# xc2401_breakout.net
KiCad netlist of a schematic drawn in EAGLE
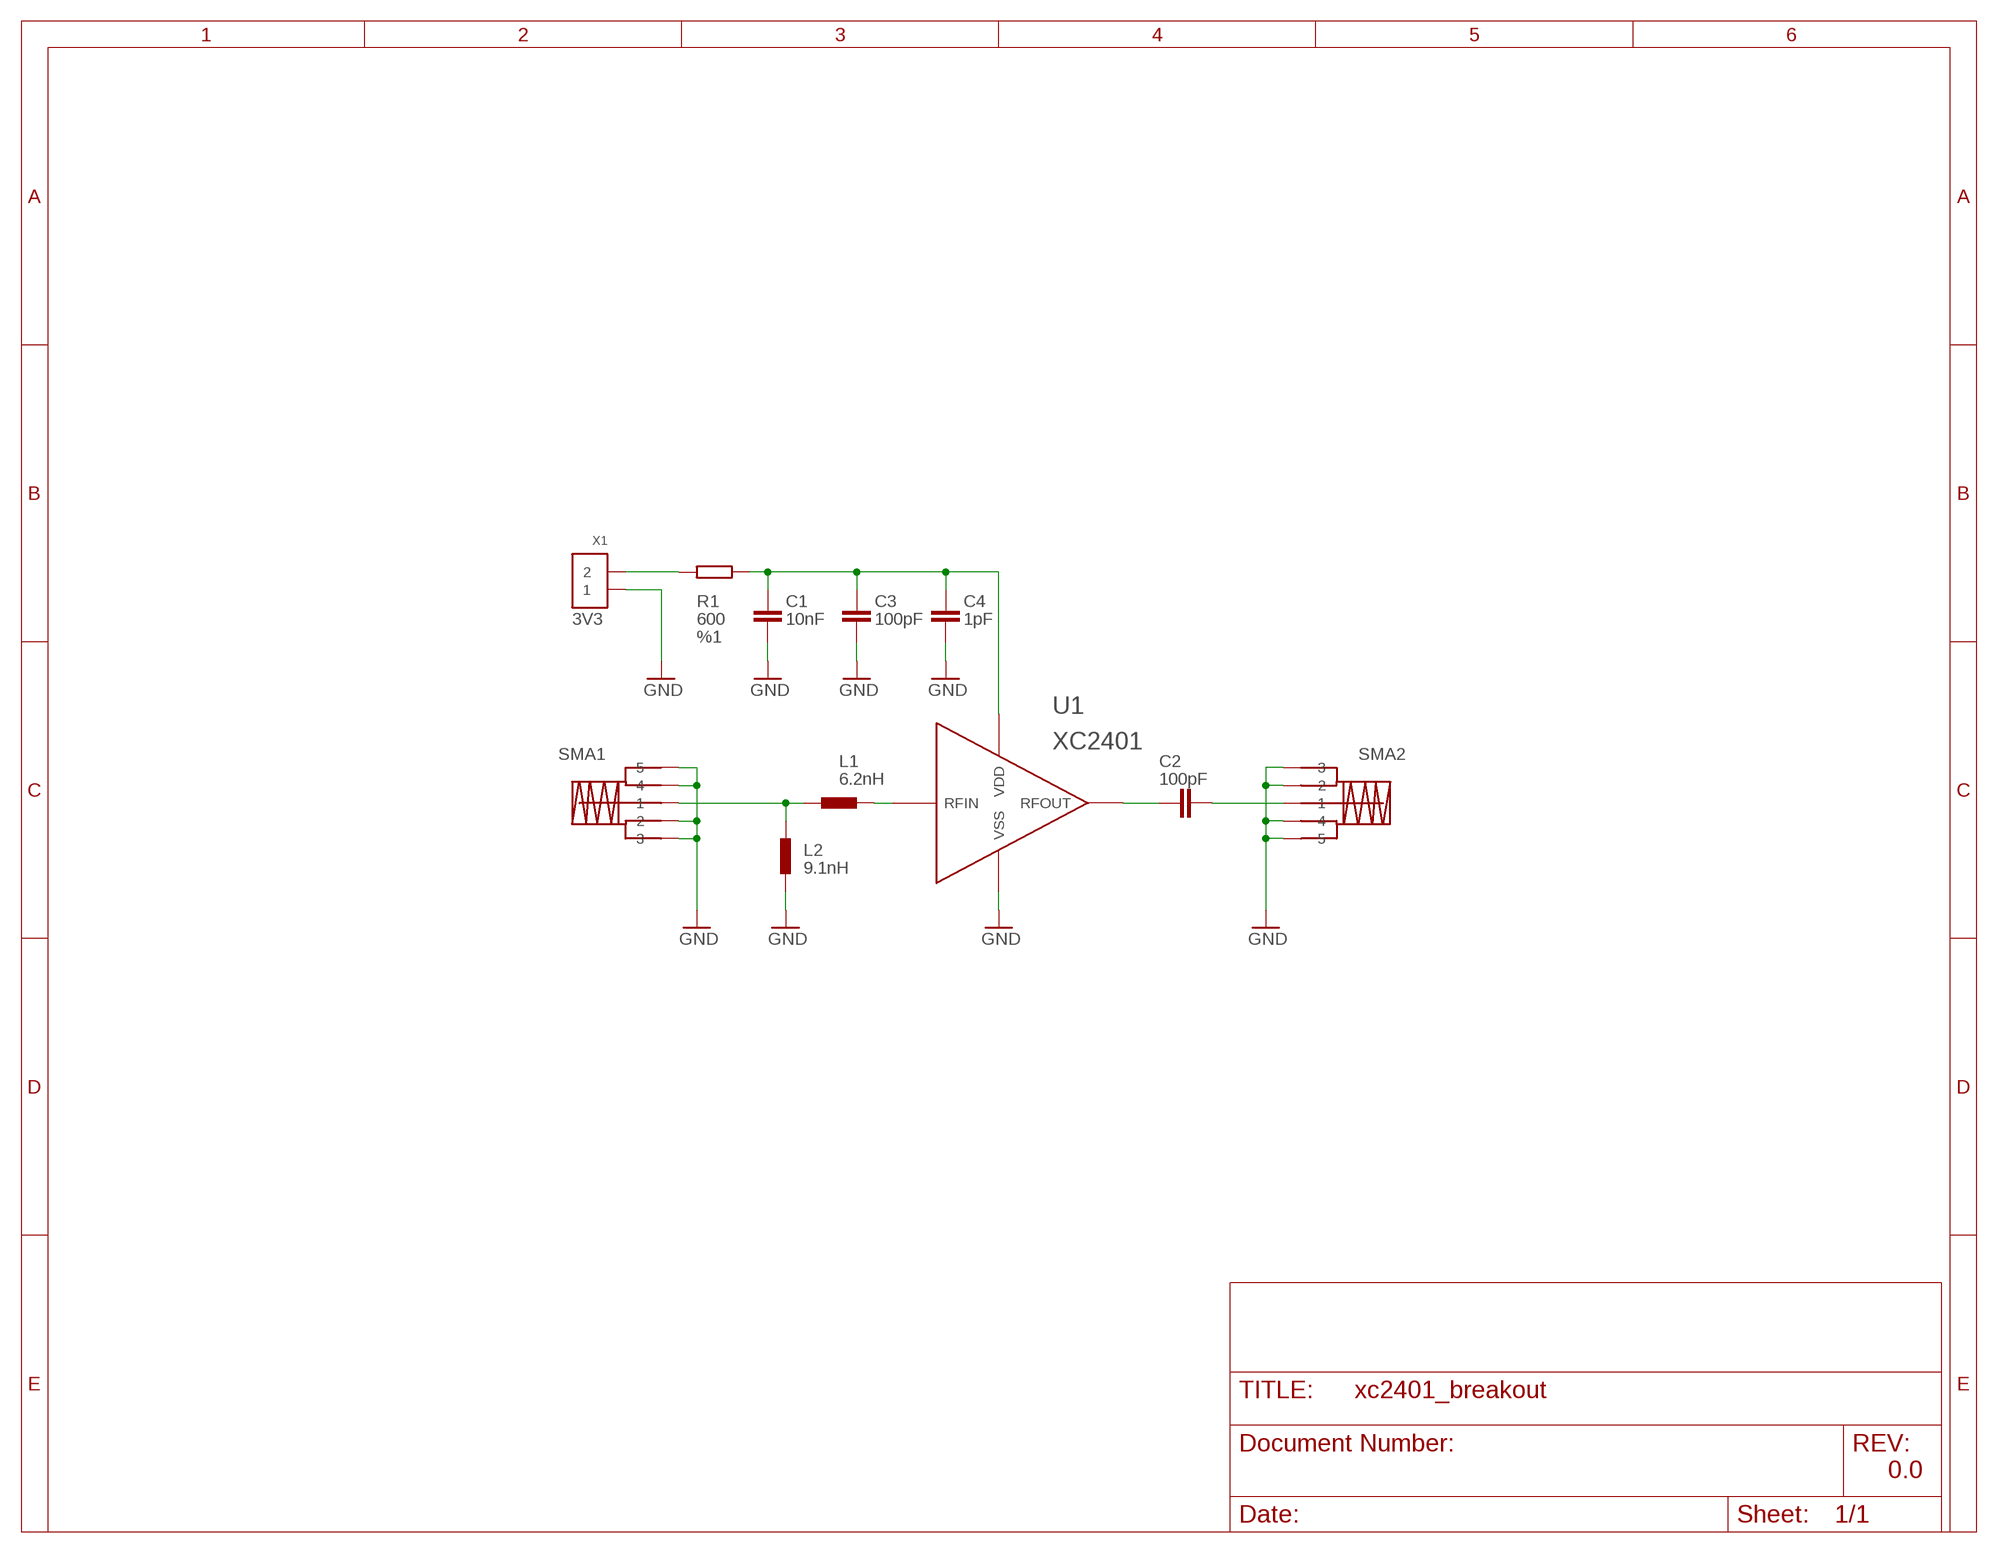
[diagram p0: schematic, sheet 1]

(export (version "E")
  (design (tool "Eeschema 10.0.6"))
  (components
    (comp (ref "C1")
      (value "10nF")
      (footprint "eagle-import:0402-CAP")
      (libsource (lib "eagle-import") (part "CAPACITOR-0402"))
    )
    (comp (ref "C2")
      (value "100pF")
      (footprint "eagle-import:0402-CAP")
      (libsource (lib "eagle-import") (part "CAPACITOR-0402"))
    )
    (comp (ref "C3")
      (value "100pF")
      (footprint "eagle-import:0402-CAP")
      (libsource (lib "eagle-import") (part "CAPACITOR-0402"))
    )
    (comp (ref "C4")
      (value "1pF")
      (footprint "eagle-import:0402-CAP")
      (libsource (lib "eagle-import") (part "CAPACITOR-0402"))
    )
    (comp (ref "L1")
      (value "6.2nH")
      (footprint "eagle-import:0402-IND")
      (libsource (lib "eagle-import") (part "INDUCTOR-0402"))
    )
    (comp (ref "L2")
      (value "9.1nH")
      (footprint "eagle-import:0402-IND")
      (libsource (lib "eagle-import") (part "INDUCTOR-0402"))
    )
    (comp (ref "R1")
      (value "600")
      (footprint "eagle-import:0402-RES")
      (libsource (lib "eagle-import") (part "RESISTOR-0402"))
    )
    (comp (ref "SMA1")
      (value "SMA_EDGE")
      (footprint "eagle-import:SMA_EDGE")
      (libsource (lib "eagle-import") (part "SMA_EDGE"))
    )
    (comp (ref "SMA2")
      (value "SMA_EDGE")
      (footprint "eagle-import:SMA_EDGE")
      (libsource (lib "eagle-import") (part "SMA_EDGE"))
    )
    (comp (ref "U1")
      (value "XC2401")
      (footprint "eagle-import:XC2401")
      (libsource (lib "eagle-import") (part "XC2401"))
    )
    (comp (ref "X1")
      (value "CONN_2-1-53261")
      (footprint "eagle-import:PB-53261-02")
      (libsource (lib "eagle-import") (part "CONN_2-1-53261"))
    )
  )
  (nets
    (net (code "1") (name "GND") (class "Default")
      (node (ref "C1") (pin "P$2") (pinfunction "2_P$2") (pintype "passive"))
      (node (ref "C3") (pin "P$2") (pinfunction "2_P$2") (pintype "passive"))
      (node (ref "C4") (pin "P$2") (pinfunction "2_P$2") (pintype "passive"))
      (node (ref "L2") (pin "P$1") (pinfunction "1_P$1") (pintype "passive"))
      (node (ref "SMA1") (pin "P2") (pinfunction "2_P2") (pintype "power_in"))
      (node (ref "SMA1") (pin "P3") (pinfunction "3_P3") (pintype "power_in"))
      (node (ref "SMA1") (pin "P4") (pinfunction "4_P4") (pintype "power_in"))
      (node (ref "SMA1") (pin "P5") (pinfunction "5_P5") (pintype "power_in"))
      (node (ref "SMA2") (pin "P2") (pinfunction "2_P2") (pintype "power_in"))
      (node (ref "SMA2") (pin "P3") (pinfunction "3_P3") (pintype "power_in"))
      (node (ref "SMA2") (pin "P4") (pinfunction "4_P4") (pintype "power_in"))
      (node (ref "SMA2") (pin "P5") (pinfunction "5_P5") (pintype "power_in"))
      (node (ref "U1") (pin "3") (pinfunction "VSS_3") (pintype "bidirectional"))
      (node (ref "X1") (pin "1") (pinfunction "1_1") (pintype "bidirectional"))
    )
    (net (code "2") (name "Net-(C1-1)") (class "Default")
      (node (ref "C1") (pin "P$1") (pinfunction "1_P$1") (pintype "passive"))
      (node (ref "C3") (pin "P$1") (pinfunction "1_P$1") (pintype "passive"))
      (node (ref "C4") (pin "P$1") (pinfunction "1_P$1") (pintype "passive"))
      (node (ref "R1") (pin "P$2") (pinfunction "2_P$2") (pintype "passive"))
      (node (ref "U1") (pin "1") (pinfunction "VDD_1") (pintype "bidirectional"))
    )
    (net (code "3") (name "Net-(C2-1)") (class "Default")
      (node (ref "C2") (pin "P$1") (pinfunction "1_P$1") (pintype "passive"))
      (node (ref "U1") (pin "2") (pinfunction "RFOUT_2") (pintype "bidirectional"))
    )
    (net (code "4") (name "Net-(C2-2)") (class "Default")
      (node (ref "C2") (pin "P$2") (pinfunction "2_P$2") (pintype "passive"))
      (node (ref "SMA2") (pin "P1") (pinfunction "1_P1") (pintype "bidirectional"))
    )
    (net (code "5") (name "Net-(L1-1)") (class "Default")
      (node (ref "L1") (pin "P$1") (pinfunction "1_P$1") (pintype "passive"))
      (node (ref "L2") (pin "P$2") (pinfunction "2_P$2") (pintype "passive"))
      (node (ref "SMA1") (pin "P1") (pinfunction "1_P1") (pintype "bidirectional"))
    )
    (net (code "6") (name "Net-(L1-2)") (class "Default")
      (node (ref "L1") (pin "P$2") (pinfunction "2_P$2") (pintype "passive"))
      (node (ref "U1") (pin "4") (pinfunction "RFIN_4") (pintype "bidirectional"))
    )
    (net (code "7") (name "Net-(R1-1)") (class "Default")
      (node (ref "R1") (pin "P$1") (pinfunction "1_P$1") (pintype "passive"))
      (node (ref "X1") (pin "2") (pinfunction "2_2") (pintype "bidirectional"))
    )
  )
)
